# Copy_of_DAC_PWW_Outputs.net
KiCad netlist of a schematic drawn in Altium Designer
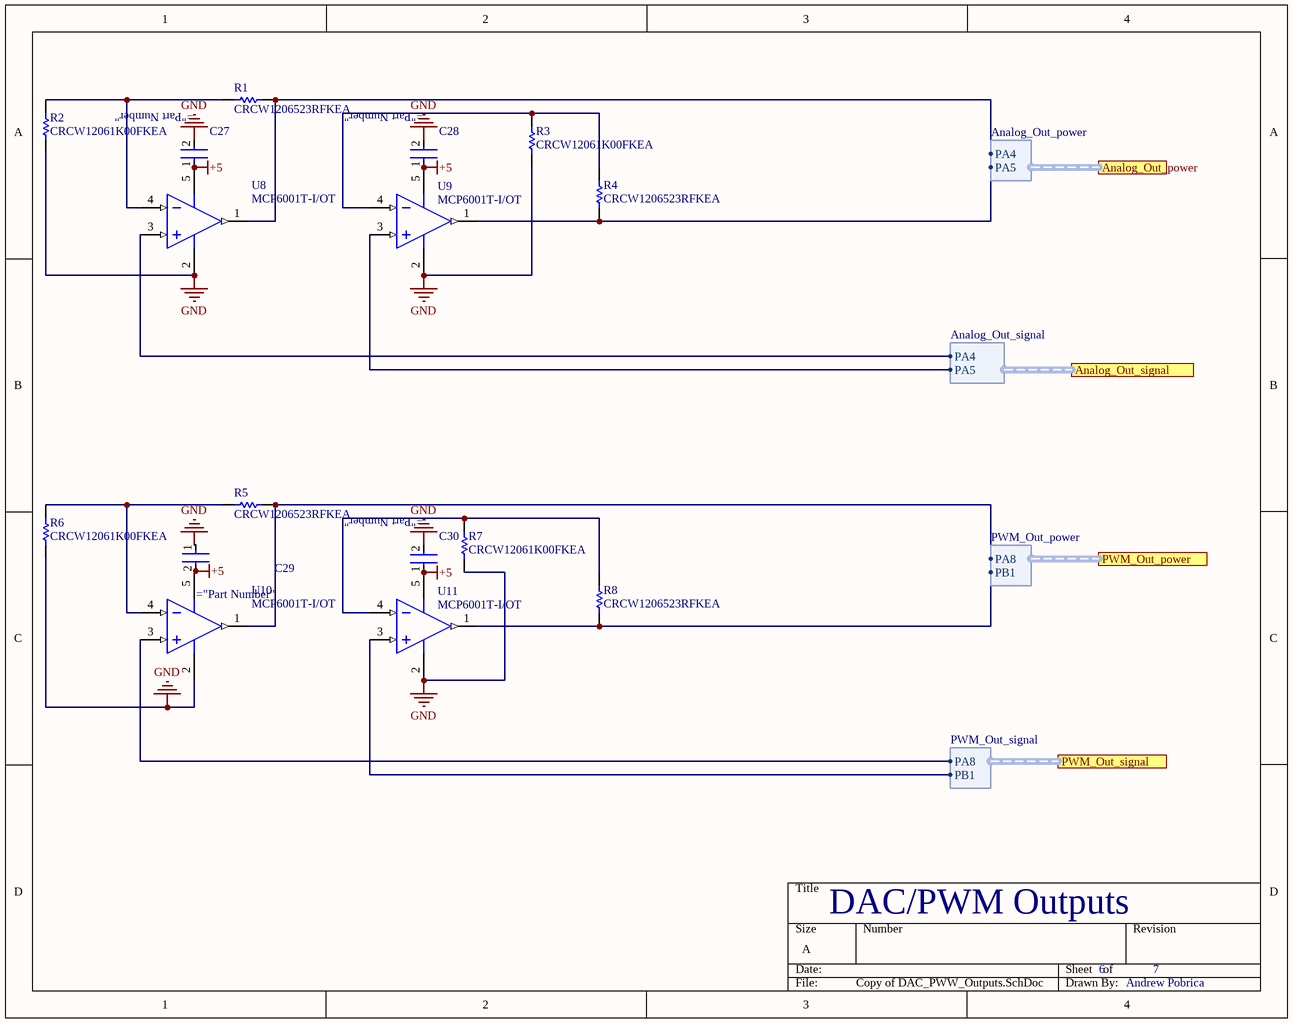
[diagram p0: Copy of DAC_PWW_Outputs.SchDoc]

(export (version "E")
  (design (tool "Eeschema 10.0.6"))
  (components
    (comp (ref "C27")
      (value "C0603C104K5RACTU")
      (footprint "Kemet_C0805_IPC_A")
      (libsource (lib "UNK_Kemet_C0603C104K5RACTU_eec") (part "C0603C104K5RACTU"))
    )
    (comp (ref "C28")
      (value "C0603C104K5RACTU")
      (footprint "Kemet_C0805_IPC_A")
      (libsource (lib "UNK_Kemet_C0603C104K5RACTU_eec") (part "C0603C104K5RACTU"))
    )
    (comp (ref "C29")
      (value "C0603C104K5RACTU")
      (footprint "Kemet_C0805_IPC_A")
      (libsource (lib "UNK_Kemet_C0603C104K5RACTU_eec") (part "C0603C104K5RACTU"))
    )
    (comp (ref "C30")
      (value "C0603C104K5RACTU")
      (footprint "Kemet_C0805_IPC_A")
      (libsource (lib "UNK_Kemet_C0603C104K5RACTU_eec") (part "C0603C104K5RACTU"))
    )
    (comp (ref "R1")
      (value "CRCW1206523RFKEA")
      (footprint "RESC3216X60X45NL10T20")
      (fields (field (name "MANUFACTURER") "Vishay Dale"))
      (libsource (lib "Altium Content Vault") (part "RES"))
    )
    (comp (ref "R2")
      (value "CRCW12061K00FKEA")
      (footprint "RESC3216X60X45ML15T20")
      (description "Chip Resistor, 1 KOhm, +/- 1%, 0.25 W, -55 to 155 degC, 1206 (3216 Metric), RoHS, Tape and Reel")
      (fields (field (name "MANUFACTURER") "Vishay Semiconductor") (field (name "TOLERANCE") "1%"))
      (libsource (lib "Altium Content Vault") (part "RES-2"))
    )
    (comp (ref "R3")
      (value "CRCW12061K00FKEA")
      (footprint "RESC3216X60X45ML15T20")
      (description "Chip Resistor, 1 KOhm, +/- 1%, 0.25 W, -55 to 155 degC, 1206 (3216 Metric), RoHS, Tape and Reel")
      (fields (field (name "MANUFACTURER") "Vishay Semiconductor") (field (name "TOLERANCE") "1%"))
      (libsource (lib "Altium Content Vault") (part "RES-2"))
    )
    (comp (ref "R4")
      (value "CRCW1206523RFKEA")
      (footprint "RESC3216X60X45NL10T20")
      (fields (field (name "MANUFACTURER") "Vishay Dale"))
      (libsource (lib "Altium Content Vault") (part "RES"))
    )
    (comp (ref "R5")
      (value "CRCW1206523RFKEA")
      (footprint "RESC3216X60X45NL10T20")
      (fields (field (name "MANUFACTURER") "Vishay Dale"))
      (libsource (lib "Altium Content Vault") (part "RES"))
    )
    (comp (ref "R6")
      (value "CRCW12061K00FKEA")
      (footprint "RESC3216X60X45ML15T20")
      (description "Chip Resistor, 1 KOhm, +/- 1%, 0.25 W, -55 to 155 degC, 1206 (3216 Metric), RoHS, Tape and Reel")
      (fields (field (name "MANUFACTURER") "Vishay Semiconductor") (field (name "TOLERANCE") "1%"))
      (libsource (lib "Altium Content Vault") (part "RES-2"))
    )
    (comp (ref "R7")
      (value "CRCW12061K00FKEA")
      (footprint "RESC3216X60X45ML15T20")
      (description "Chip Resistor, 1 KOhm, +/- 1%, 0.25 W, -55 to 155 degC, 1206 (3216 Metric), RoHS, Tape and Reel")
      (fields (field (name "MANUFACTURER") "Vishay Semiconductor") (field (name "TOLERANCE") "1%"))
      (libsource (lib "Altium Content Vault") (part "RES-2"))
    )
    (comp (ref "R8")
      (value "CRCW1206523RFKEA")
      (footprint "RESC3216X60X45NL10T20")
      (fields (field (name "MANUFACTURER") "Vishay Dale"))
      (libsource (lib "Altium Content Vault") (part "RES"))
    )
    (comp (ref "U8")
      (value "MCP6001T-I/OT")
      (footprint "SOT-23-OT5_CUSTOM")
      (description "1 MHz, Low-Power Operational Amplifier, 5-Pin SOT-23, Industrial Temperature, Tape and Reel")
      (libsource (lib "Components - 19.05.19 - 16.13") (part "AMP-OPA-MCP6001-SOT5"))
    )
    (comp (ref "U9")
      (value "MCP6001T-I/OT")
      (footprint "SOT-23-OT5_CUSTOM")
      (description "1 MHz, Low-Power Operational Amplifier, 5-Pin SOT-23, Industrial Temperature, Tape and Reel")
      (libsource (lib "Components - 19.05.19 - 16.13") (part "AMP-OPA-MCP6001-SOT5"))
    )
    (comp (ref "U10")
      (value "MCP6001T-I/OT")
      (footprint "SOT-23-OT5_CUSTOM")
      (description "1 MHz, Low-Power Operational Amplifier, 5-Pin SOT-23, Industrial Temperature, Tape and Reel")
      (libsource (lib "Components - 19.05.19 - 16.13") (part "AMP-OPA-MCP6001-SOT5"))
    )
    (comp (ref "U11")
      (value "MCP6001T-I/OT")
      (footprint "SOT-23-OT5_CUSTOM")
      (description "1 MHz, Low-Power Operational Amplifier, 5-Pin SOT-23, Industrial Temperature, Tape and Reel")
      (libsource (lib "Components - 19.05.19 - 16.13") (part "AMP-OPA-MCP6001-SOT5"))
    )
  )
  (nets
    (net (code "5") (name "+5") (class "Default")
      (node (ref "C27") (pin "1") (pinfunction "1_1") (pintype "passive"))
      (node (ref "C28") (pin "1") (pinfunction "1_1") (pintype "passive"))
      (node (ref "C29") (pin "2") (pinfunction "2_2") (pintype "passive"))
      (node (ref "C30") (pin "1") (pinfunction "1_1") (pintype "passive"))
      (node (ref "U10") (pin "5") (pinfunction "VDD_5") (pintype "power_in"))
      (node (ref "U11") (pin "5") (pinfunction "VDD_5") (pintype "power_in"))
      (node (ref "U8") (pin "5") (pinfunction "VDD_5") (pintype "power_in"))
      (node (ref "U9") (pin "5") (pinfunction "VDD_5") (pintype "power_in"))
    )
    (net (code "10") (name "GND") (class "Default")
      (node (ref "C27") (pin "2") (pinfunction "2_2") (pintype "passive"))
      (node (ref "C28") (pin "2") (pinfunction "2_2") (pintype "passive"))
      (node (ref "C29") (pin "1") (pinfunction "1_1") (pintype "passive"))
      (node (ref "C30") (pin "2") (pinfunction "2_2") (pintype "passive"))
      (node (ref "R2") (pin "2") (pinfunction "2_2") (pintype "passive"))
      (node (ref "R3") (pin "2") (pinfunction "2_2") (pintype "passive"))
      (node (ref "R6") (pin "2") (pinfunction "2_2") (pintype "passive"))
      (node (ref "R7") (pin "2") (pinfunction "2_2") (pintype "passive"))
      (node (ref "U10") (pin "2") (pinfunction "VSS_2") (pintype "power_in"))
      (node (ref "U11") (pin "2") (pinfunction "VSS_2") (pintype "power_in"))
      (node (ref "U8") (pin "2") (pinfunction "VSS_2") (pintype "power_in"))
      (node (ref "U9") (pin "2") (pinfunction "VSS_2") (pintype "power_in"))
    )
    (net (code "11") (name "Net-(U8-VIN-)") (class "Default")
      (node (ref "R1") (pin "2") (pinfunction "2_2") (pintype "passive"))
      (node (ref "R2") (pin "1") (pinfunction "1_1") (pintype "passive"))
      (node (ref "U8") (pin "4") (pinfunction "VIN-_4") (pintype "input"))
    )
    (net (code "12") (name "Net-(U8-VOUT)") (class "Default")
      (node (ref "R1") (pin "1") (pinfunction "1_1") (pintype "passive"))
      (node (ref "U8") (pin "1") (pinfunction "VOUT_1") (pintype "output"))
    )
    (net (code "13") (name "Net-(U9-VIN-)") (class "Default")
      (node (ref "R3") (pin "1") (pinfunction "1_1") (pintype "passive"))
      (node (ref "R4") (pin "2") (pinfunction "2_2") (pintype "passive"))
      (node (ref "U9") (pin "4") (pinfunction "VIN-_4") (pintype "input"))
    )
    (net (code "14") (name "Net-(U9-VOUT)") (class "Default")
      (node (ref "R4") (pin "1") (pinfunction "1_1") (pintype "passive"))
      (node (ref "U9") (pin "1") (pinfunction "VOUT_1") (pintype "output"))
    )
    (net (code "15") (name "Net-(U10-VIN-)") (class "Default")
      (node (ref "R5") (pin "2") (pinfunction "2_2") (pintype "passive"))
      (node (ref "R6") (pin "1") (pinfunction "1_1") (pintype "passive"))
      (node (ref "U10") (pin "4") (pinfunction "VIN-_4") (pintype "input"))
    )
    (net (code "16") (name "Net-(U10-VOUT)") (class "Default")
      (node (ref "R5") (pin "1") (pinfunction "1_1") (pintype "passive"))
      (node (ref "U10") (pin "1") (pinfunction "VOUT_1") (pintype "output"))
    )
    (net (code "17") (name "Net-(U11-VIN-)") (class "Default")
      (node (ref "R7") (pin "1") (pinfunction "1_1") (pintype "passive"))
      (node (ref "R8") (pin "2") (pinfunction "2_2") (pintype "passive"))
      (node (ref "U11") (pin "4") (pinfunction "VIN-_4") (pintype "input"))
    )
    (net (code "18") (name "Net-(U11-VOUT)") (class "Default")
      (node (ref "R8") (pin "1") (pinfunction "1_1") (pintype "passive"))
      (node (ref "U11") (pin "1") (pinfunction "VOUT_1") (pintype "output"))
    )
    (net (code "19") (name "unconnected-(U8-VIN+-Pad3)") (class "Default")
      (node (ref "U8") (pin "3") (pinfunction "VIN+_3") (pintype "input"))
    )
    (net (code "20") (name "unconnected-(U9-VIN+-Pad3)") (class "Default")
      (node (ref "U9") (pin "3") (pinfunction "VIN+_3") (pintype "input"))
    )
    (net (code "21") (name "unconnected-(U10-VIN+-Pad3)") (class "Default")
      (node (ref "U10") (pin "3") (pinfunction "VIN+_3") (pintype "input"))
    )
    (net (code "22") (name "unconnected-(U11-VIN+-Pad3)") (class "Default")
      (node (ref "U11") (pin "3") (pinfunction "VIN+_3") (pintype "input"))
    )
  )
)
